# MotherBoard.net
KiCad netlist of a schematic drawn in Altium Designer
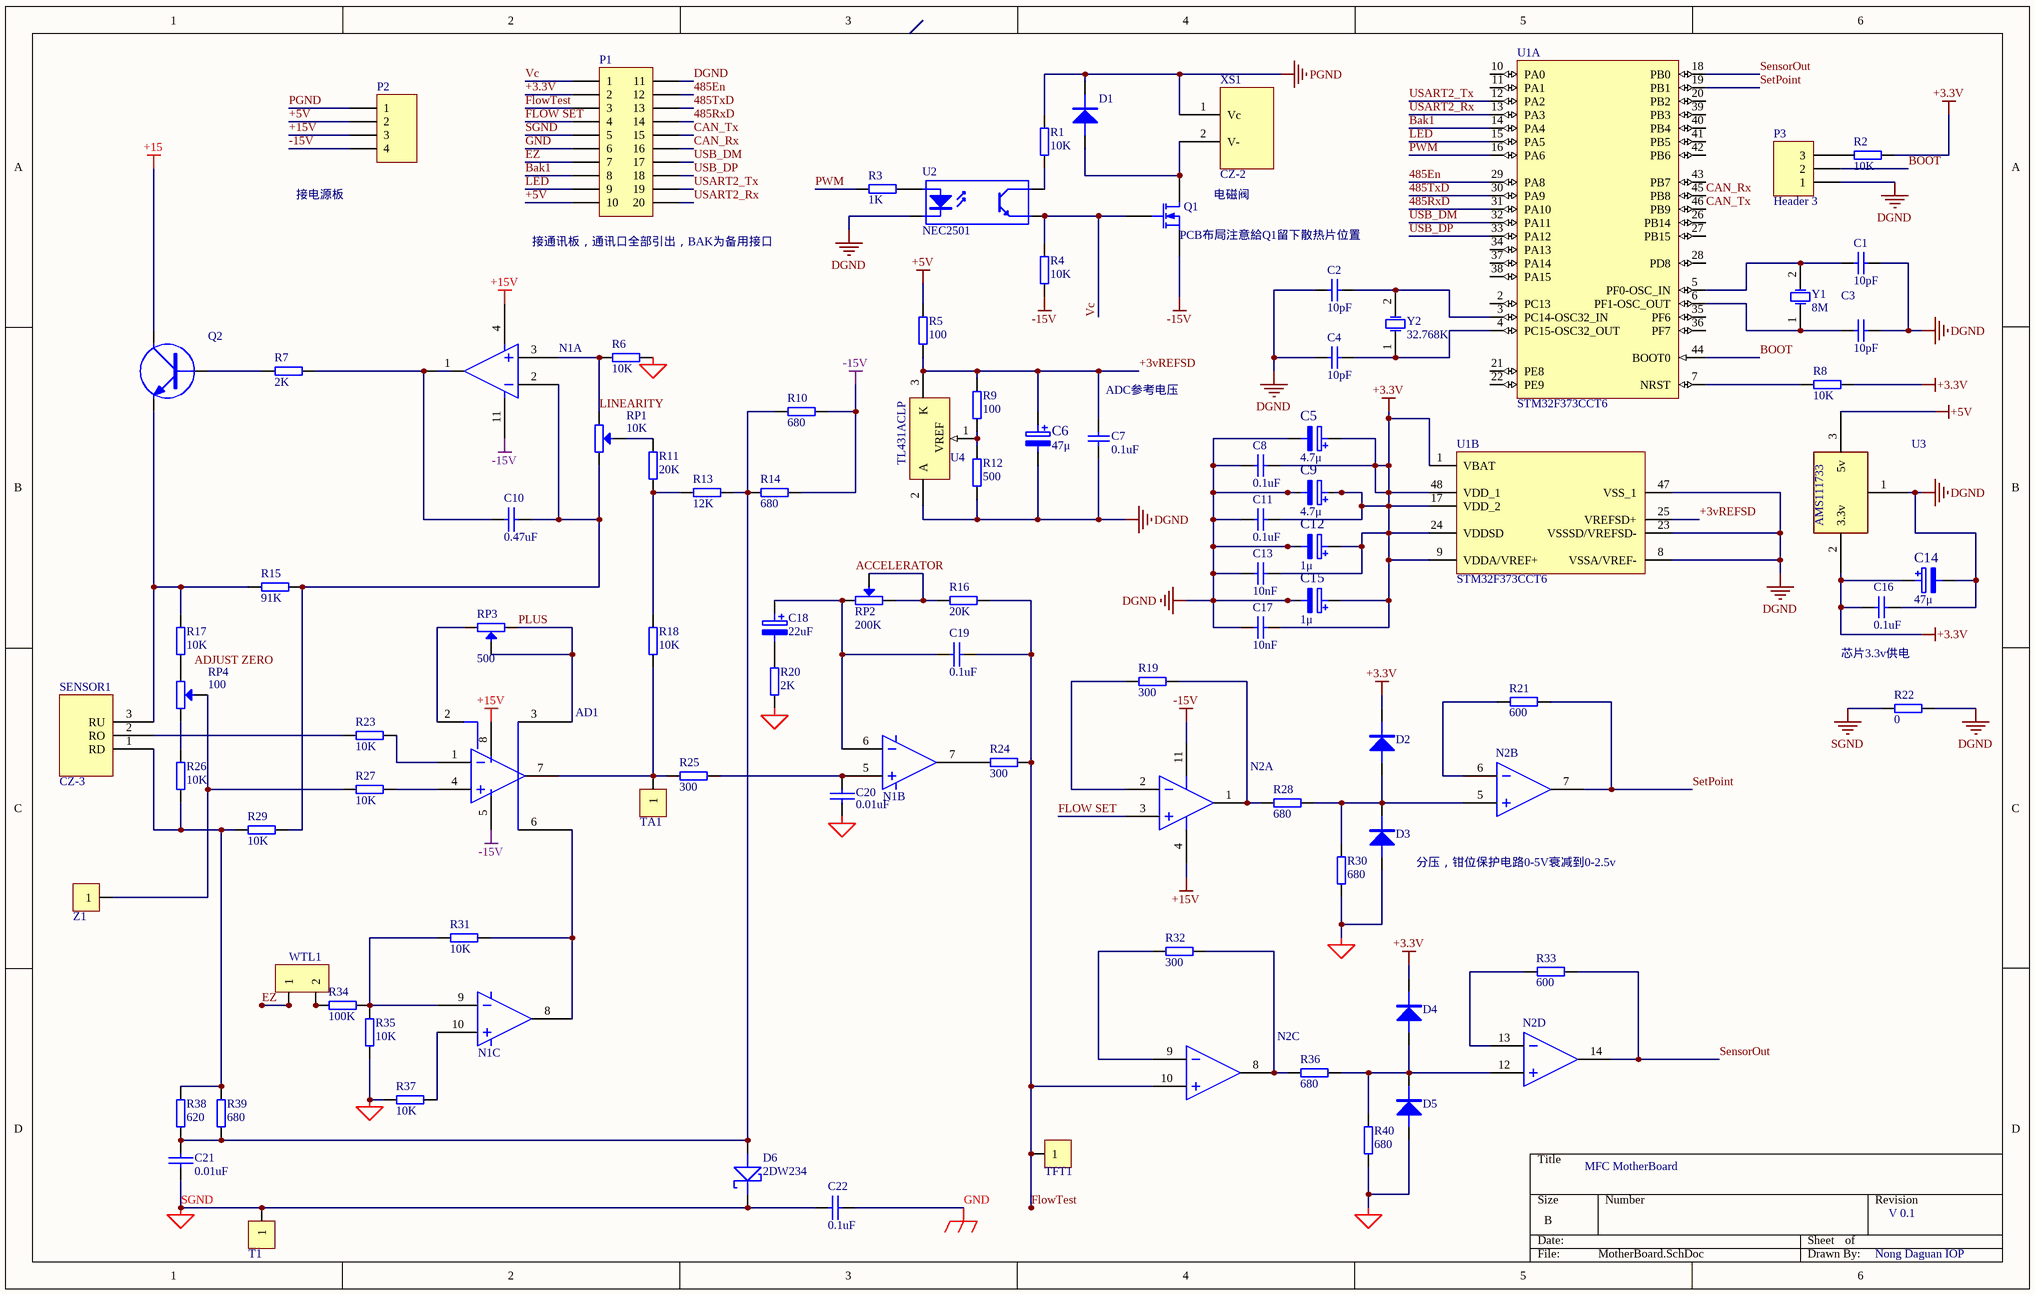
[diagram p0: MotherBoard.SchDoc]

(export (version "E")
  (design (tool "Eeschema 10.0.6"))
  (components
    (comp (ref "AD1") (value "~") (footprint "SO-8") (libsource (lib "1.60") (part "AD8221")))
    (comp (ref "C1")
      (value "10pF")
      (footprint "R.4")
      (description "Capacitor")
      (fields (field (name "PUBLISHER") "Altium Limited"))
      (libsource (lib "1.60") (part "Cap"))
    )
    (comp (ref "C2")
      (value "10pF")
      (footprint "R.4")
      (description "Capacitor")
      (fields (field (name "PUBLISHER") "Altium Limited"))
      (libsource (lib "1.60") (part "Cap"))
    )
    (comp (ref "C3")
      (value "10pF")
      (footprint "R.4")
      (description "Capacitor")
      (fields (field (name "PUBLISHER") "Altium Limited"))
      (libsource (lib "1.60") (part "Cap"))
    )
    (comp (ref "C4")
      (value "10pF")
      (footprint "R.4")
      (description "Capacitor")
      (fields (field (name "PUBLISHER") "Altium Limited"))
      (libsource (lib "1.60") (part "Cap"))
    )
    (comp (ref "C5") (value "4.7μ") (footprint "CA-22U") (libsource (lib "1.60") (part "ELECTRO2")))
    (comp (ref "C6") (value "47μ") (footprint "CA-22U") (libsource (lib "1.60") (part "ELECTRO2")))
    (comp (ref "C7")
      (value "0.1uF")
      (footprint "R.4")
      (description "Capacitor")
      (fields (field (name "PUBLISHER") "Altium Limited"))
      (libsource (lib "1.60") (part "Cap"))
    )
    (comp (ref "C8")
      (value "0.1uF")
      (footprint "R.4")
      (description "Capacitor")
      (fields (field (name "PUBLISHER") "Altium Limited"))
      (libsource (lib "1.60") (part "Cap"))
    )
    (comp (ref "C9") (value "4.7μ") (footprint "CA-22U") (libsource (lib "1.60") (part "ELECTRO2")))
    (comp (ref "C10") (value "0.47uF") (footprint "R.4") (libsource (lib "1.60") (part "CAP")))
    (comp (ref "C11")
      (value "0.1uF")
      (footprint "R.4")
      (description "Capacitor")
      (fields (field (name "PUBLISHER") "Altium Limited"))
      (libsource (lib "1.60") (part "Cap"))
    )
    (comp (ref "C12") (value "1μ") (footprint "CA-22U") (libsource (lib "1.60") (part "ELECTRO2")))
    (comp (ref "C13")
      (value "10nF")
      (footprint "R.4")
      (description "Capacitor")
      (fields (field (name "PUBLISHER") "Altium Limited"))
      (libsource (lib "1.60") (part "Cap"))
    )
    (comp (ref "C14") (value "47μ") (footprint "CA-22U") (libsource (lib "1.60") (part "ELECTRO2")))
    (comp (ref "C15") (value "1μ") (footprint "CA-22U") (libsource (lib "1.60") (part "ELECTRO2")))
    (comp (ref "C16")
      (value "0.1uF")
      (footprint "R.4")
      (description "Capacitor")
      (fields (field (name "PUBLISHER") "Altium Limited"))
      (libsource (lib "1.60") (part "Cap"))
    )
    (comp (ref "C17")
      (value "10nF")
      (footprint "R.4")
      (description "Capacitor")
      (fields (field (name "PUBLISHER") "Altium Limited"))
      (libsource (lib "1.60") (part "Cap"))
    )
    (comp (ref "C18") (value "22uF") (footprint "CA-22U") (libsource (lib "1.60") (part "ELECTRO2")))
    (comp (ref "C19") (value "0.1uF") (footprint "R.4") (libsource (lib "1.60") (part "CAP")))
    (comp (ref "C20") (value "0.01uF") (footprint "R.4") (libsource (lib "1.60") (part "CAP")))
    (comp (ref "C21") (value "0.01uF") (footprint "R.4") (libsource (lib "1.60") (part "CAP")))
    (comp (ref "C22") (value "0.1uF") (footprint "R.4") (libsource (lib "1.60") (part "CAP")))
    (comp (ref "D1") (value "2CK73C") (footprint "V.4") (libsource (lib "1.60") (part "DIODE")))
    (comp (ref "D2") (value "2CK73C") (footprint "DIODE") (libsource (lib "1.60") (part "DIODE")))
    (comp (ref "D3") (value "2CK73C") (footprint "DIODE") (libsource (lib "1.60") (part "DIODE")))
    (comp (ref "D4") (value "2CK73C") (footprint "DIODE") (libsource (lib "1.60") (part "DIODE")))
    (comp (ref "D5") (value "2CK73C") (footprint "DIODE") (libsource (lib "1.60") (part "DIODE")))
    (comp (ref "D6") (value "2DW234") (footprint "zena") (libsource (lib "1.90") (part "DIODE SCHOTTKY")))
    (comp (ref "N1") (value "LM124") (footprint "SO-14") (libsource (lib "*") (part "MFC7A.S01_LM124_56")))
    (comp (ref "N2") (value "LM124") (footprint "SO-14") (libsource (lib "1.60") (part "LM1241")))
    (comp (ref "P1")
      (value "~")
      (footprint "HDR2X10_CEN")
      (description "Header, 10-Pin, Dual row")
      (fields (field (name "PUBLISHER") "Altium Limited"))
      (libsource (lib "Miscellaneous Connectors") (part "Header 10X2A"))
    )
    (comp (ref "P2")
      (value "~")
      (footprint "HDR1X4")
      (description "Header, 4-Pin")
      (fields (field (name "PUBLISHER") "Altium Limited"))
      (libsource (lib "Miscellaneous Connectors") (part "Header 4"))
    )
    (comp (ref "P3")
      (value "Header 3")
      (footprint "HDR1X3")
      (description "Header, 3-Pin")
      (fields (field (name "PUBLISHER") "Altium Limited"))
      (libsource (lib "Miscellaneous Connectors") (part "Header 3"))
    )
    (comp (ref "Q1")
      (value "MOSFET-N")
      (footprint "TO-220AB")
      (description "N-Channel MOSFET")
      (fields (field (name "PUBLISHER") "Altium Limited"))
      (libsource (lib "Miscellaneous Devices") (part "MOSFET-N"))
    )
    (comp (ref "Q2") (value "MC9013") (footprint "BJT") (libsource (lib "1.60") (part "MC9013")))
    (comp (ref "R1") (value "10K") (footprint "R.4") (libsource (lib "1.60") (part "RES_1")))
    (comp (ref "R2") (value "10K") (footprint "R.4") (libsource (lib "1.60") (part "RES_1")))
    (comp (ref "R3") (value "1K") (footprint "R.4") (libsource (lib "1.60") (part "RES_1")))
    (comp (ref "R4") (value "10K") (footprint "R.4") (libsource (lib "1.60") (part "RES_1")))
    (comp (ref "R5") (value "100") (footprint "R.4") (libsource (lib "1.60") (part "RES_1")))
    (comp (ref "R6") (value "10K") (footprint "R.4") (libsource (lib "1.60") (part "RES_1")))
    (comp (ref "R7") (value "2K") (footprint "R.4") (libsource (lib "1.60") (part "RES_1")))
    (comp (ref "R8") (value "10K") (footprint "R.4") (libsource (lib "1.60") (part "RES_1")))
    (comp (ref "R9") (value "100") (footprint "RAD0.1") (libsource (lib "1.60") (part "RES")))
    (comp (ref "R10") (value "680") (footprint "R.4") (libsource (lib "1.60") (part "RES_1")))
    (comp (ref "R11") (value "20K") (footprint "R.4") (libsource (lib "1.60") (part "RES_1")))
    (comp (ref "R12") (value "500") (footprint "RAD0.1") (libsource (lib "1.60") (part "RES")))
    (comp (ref "R13") (value "12K") (footprint "R.4") (libsource (lib "1.60") (part "RES_1")))
    (comp (ref "R14") (value "680") (footprint "R.4") (libsource (lib "1.60") (part "RES_1")))
    (comp (ref "R15") (value "91K") (footprint "R.4") (libsource (lib "1.60") (part "RES_1")))
    (comp (ref "R16") (value "20K") (footprint "R.4") (libsource (lib "1.60") (part "RES_1")))
    (comp (ref "R17") (value "10K") (footprint "RAD0.1") (libsource (lib "1.60") (part "RES")))
    (comp (ref "R18") (value "10K") (footprint "R.4") (libsource (lib "1.60") (part "RES_1")))
    (comp (ref "R19") (value "300") (footprint "R.4") (libsource (lib "1.60") (part "RES_1")))
    (comp (ref "R20") (value "2K") (footprint "R.4") (libsource (lib "1.60") (part "RES_1")))
    (comp (ref "R21") (value "600") (footprint "R.4") (libsource (lib "1.60") (part "RES_1")))
    (comp (ref "R22") (value "0") (footprint "R.4") (libsource (lib "1.60") (part "RES_1")))
    (comp (ref "R23") (value "10K") (footprint "R.4") (libsource (lib "1.60") (part "RES_1")))
    (comp (ref "R24") (value "300") (footprint "R.4") (libsource (lib "1.60") (part "RES_1")))
    (comp (ref "R25") (value "300") (footprint "R.4") (libsource (lib "1.60") (part "RES_1")))
    (comp (ref "R26") (value "10K") (footprint "RAD0.1") (libsource (lib "1.60") (part "RES")))
    (comp (ref "R27") (value "10K") (footprint "R.4") (libsource (lib "1.60") (part "RES_1")))
    (comp (ref "R28") (value "680") (footprint "RAD0.1") (libsource (lib "1.60") (part "RES")))
    (comp (ref "R29") (value "10K") (footprint "R.4") (libsource (lib "1.60") (part "RES_1")))
    (comp (ref "R30") (value "680") (footprint "RAD0.1") (libsource (lib "1.60") (part "RES")))
    (comp (ref "R31") (value "10K") (footprint "R.4") (libsource (lib "1.60") (part "RES_1")))
    (comp (ref "R32") (value "300") (footprint "R.4") (libsource (lib "1.60") (part "RES_1")))
    (comp (ref "R33") (value "600") (footprint "R.4") (libsource (lib "1.60") (part "RES_1")))
    (comp (ref "R34") (value "100K") (footprint "R.4") (libsource (lib "1.60") (part "RES_1")))
    (comp (ref "R35") (value "10K") (footprint "R.4") (libsource (lib "1.60") (part "RES_1")))
    (comp (ref "R36") (value "680") (footprint "RAD0.1") (libsource (lib "1.60") (part "RES")))
    (comp (ref "R37") (value "10K") (footprint "R.4") (libsource (lib "1.60") (part "RES_1")))
    (comp (ref "R38") (value "620") (footprint "RAD0.1") (libsource (lib "1.60") (part "RES")))
    (comp (ref "R39") (value "680") (footprint "RAD0.1") (libsource (lib "1.60") (part "RES")))
    (comp (ref "R40") (value "680") (footprint "RAD0.1") (libsource (lib "1.60") (part "RES")))
    (comp (ref "RP1") (value "10K") (footprint "VR5132") (libsource (lib "1.60") (part "POT2")))
    (comp (ref "RP2")
      (value "200K")
      (footprint "changable res")
      (description "3362")
      (libsource (lib "1.60") (part "POT2"))
    )
    (comp (ref "RP3") (value "500") (footprint "VR5132") (libsource (lib "1.60") (part "POT2")))
    (comp (ref "RP4") (value "100") (footprint "VR5132") (libsource (lib "1.60") (part "POT2")))
    (comp (ref "SENSOR1") (value "CZ-3") (footprint "SENSOR") (libsource (lib "1.60") (part "CZ-3")))
    (comp (ref "T1") (value "CON1") (footprint "PAD - RECT") (libsource (lib "1.60") (part "CON1")))
    (comp (ref "TA1") (value "CON1") (footprint "PAD - RECT") (libsource (lib "1.60") (part "CON1")))
    (comp (ref "TFT1") (value "CON1") (footprint "PAD - RECT") (libsource (lib "") (part "CON1_1")))
    (comp (ref "U1")
      (value "STM32F373CCT6")
      (footprint "STM-LQFP48_N")
      (libsource (lib "1.60") (part "STM32F373CCT6"))
    )
    (comp (ref "U2")
      (value "NEC2501")
      (footprint "DIP-4")
      (description "4-Pin Phototransistor Optocoupler")
      (fields (field (name "PUBLISHER") "Altium Limited"))
      (libsource (lib "Miscellaneous Devices") (part "Optoisolator1"))
    )
    (comp (ref "U3") (value "AMS111733") (footprint "SOT223_N") (libsource (lib "1.60") (part "TL431")))
    (comp (ref "U4")
      (value "TL431ACLP")
      (footprint "LP03")
      (description "Adjustable Precision Shunt Regulator")
      (fields (field (name "PUBLISHER") "Altium Limited"))
      (libsource (lib "1.60") (part "TL431ACLP"))
    )
    (comp (ref "WTL1") (value "CON1") (footprint "ADJ") (libsource (lib "1.60") (part "CON1_1")))
    (comp (ref "XS1") (value "CZ-2") (footprint "VALVE") (libsource (lib "1.60") (part "CZ-2")))
    (comp (ref "Y1")
      (value "8M")
      (footprint "XTAL1")
      (description "Crystal Oscillator")
      (fields (field (name "PUBLISHER") "Altium Limited"))
      (libsource (lib "1.60") (part "XTAL"))
    )
    (comp (ref "Y2")
      (value "32.768K")
      (footprint "XTAL1")
      (description "Crystal Oscillator")
      (fields (field (name "PUBLISHER") "Altium Limited"))
      (libsource (lib "1.60") (part "XTAL"))
    )
    (comp (ref "Z1") (value "CON1") (footprint "PAD - RECT") (libsource (lib "") (part "CON1_2")))
  )
  (nets
    (net (code "1") (name "+3.3V") (class "Default")
      (node (ref "C11") (pin "2") (pinfunction "2_2") (pintype "passive"))
      (node (ref "C12") (pin "1") (pintype "passive"))
      (node (ref "C13") (pin "2") (pinfunction "2_2") (pintype "passive"))
      (node (ref "C14") (pin "1") (pintype "passive"))
      (node (ref "C15") (pin "1") (pintype "passive"))
      (node (ref "C16") (pin "1") (pinfunction "1_1") (pintype "passive"))
      (node (ref "C17") (pin "2") (pinfunction "2_2") (pintype "passive"))
      (node (ref "C5") (pin "1") (pintype "passive"))
      (node (ref "C8") (pin "2") (pinfunction "2_2") (pintype "passive"))
      (node (ref "C9") (pin "1") (pintype "passive"))
      (node (ref "D2") (pin "K") (pintype "passive"))
      (node (ref "D4") (pin "K") (pintype "passive"))
      (node (ref "P1") (pin "2") (pinfunction "2_2") (pintype "passive"))
      (node (ref "R2") (pin "2") (pintype "passive"))
      (node (ref "R8") (pin "2") (pintype "passive"))
      (node (ref "U1") (pin "1") (pinfunction "VBAT_1") (pintype "power_in"))
      (node (ref "U1") (pin "17") (pinfunction "VDD_2_17") (pintype "power_in"))
      (node (ref "U1") (pin "24") (pinfunction "VDDSD_24") (pintype "power_in"))
      (node (ref "U1") (pin "48") (pinfunction "VDD_1_48") (pintype "power_in"))
      (node (ref "U1") (pin "9") (pinfunction "VDDA/VREF+_9") (pintype "power_in"))
      (node (ref "U3") (pin "2") (pinfunction "3.3v_2") (pintype "passive"))
    )
    (net (code "2") (name "+5V") (class "Default")
      (node (ref "P1") (pin "10") (pinfunction "10_10") (pintype "passive"))
      (node (ref "P2") (pin "2") (pinfunction "2_2") (pintype "passive"))
      (node (ref "R5") (pin "2") (pintype "passive"))
      (node (ref "U3") (pin "3") (pinfunction "5v_3") (pintype "passive"))
    )
    (net (code "3") (name "+15") (class "Default")
      (node (ref "Q2") (pin "C") (pinfunction "C_C") (pintype "passive"))
    )
    (net (code "4") (name "+15V") (class "Default")
      (node (ref "AD1") (pin "8") (pinfunction "8_8") (pintype "passive"))
      (node (ref "N1") (pin "4") (pintype "passive"))
      (node (ref "N2") (pin "4") (pinfunction "V+_4") (pintype "passive"))
      (node (ref "P2") (pin "3") (pinfunction "3_3") (pintype "passive"))
    )
    (net (code "5") (name "-15V") (class "Default")
      (node (ref "AD1") (pin "5") (pinfunction "5_5") (pintype "passive"))
      (node (ref "N1") (pin "11") (pintype "passive"))
      (node (ref "N2") (pin "11") (pinfunction "GND_11") (pintype "passive"))
      (node (ref "P2") (pin "4") (pinfunction "4_4") (pintype "passive"))
      (node (ref "Q1") (pin "3") (pinfunction "S_3") (pintype "passive"))
      (node (ref "R10") (pin "2") (pintype "passive"))
      (node (ref "R14") (pin "2") (pintype "passive"))
      (node (ref "R4") (pin "1") (pintype "passive"))
    )
    (net (code "6") (name "/+3vREFSD") (class "Default")
      (node (ref "C6") (pin "1") (pintype "passive"))
      (node (ref "C7") (pin "2") (pinfunction "2_2") (pintype "passive"))
      (node (ref "R5") (pin "1") (pintype "passive"))
      (node (ref "R9") (pin "1") (pintype "passive"))
      (node (ref "U1") (pin "25") (pinfunction "VREFSD+_25") (pintype "power_in"))
      (node (ref "U4") (pin "3") (pinfunction "K_3") (pintype "power_in"))
    )
    (net (code "7") (name "/485En") (class "Default")
      (node (ref "P1") (pin "12") (pinfunction "12_12") (pintype "passive"))
      (node (ref "U1") (pin "29") (pinfunction "PA8_29") (pintype "bidirectional"))
    )
    (net (code "8") (name "/485RxD") (class "Default")
      (node (ref "P1") (pin "14") (pinfunction "14_14") (pintype "passive"))
      (node (ref "U1") (pin "31") (pinfunction "PA10_31") (pintype "bidirectional"))
    )
    (net (code "9") (name "/485TxD") (class "Default")
      (node (ref "P1") (pin "13") (pinfunction "13_13") (pintype "passive"))
      (node (ref "U1") (pin "30") (pinfunction "PA9_30") (pintype "bidirectional"))
    )
    (net (code "11") (name "/BOOT") (class "Default")
      (node (ref "P3") (pin "2") (pinfunction "2_2") (pintype "passive"))
      (node (ref "U1") (pin "44") (pinfunction "BOOT0_44") (pintype "input"))
    )
    (net (code "12") (name "/Bak1") (class "Default")
      (node (ref "P1") (pin "8") (pinfunction "8_8") (pintype "passive"))
      (node (ref "U1") (pin "14") (pinfunction "PA4_14") (pintype "bidirectional"))
    )
    (net (code "13") (name "/CAN_Rx") (class "Default")
      (node (ref "P1") (pin "16") (pinfunction "16_16") (pintype "passive"))
      (node (ref "U1") (pin "45") (pinfunction "PB8_45") (pintype "bidirectional"))
    )
    (net (code "14") (name "/CAN_Tx") (class "Default")
      (node (ref "P1") (pin "15") (pinfunction "15_15") (pintype "passive"))
      (node (ref "U1") (pin "46") (pinfunction "PB9_46") (pintype "bidirectional"))
    )
    (net (code "15") (name "/EZ") (class "Default")
      (node (ref "P1") (pin "7") (pinfunction "7_7") (pintype "passive"))
      (node (ref "WTL1") (pin "1") (pinfunction "1_1") (pintype "passive"))
    )
    (net (code "16") (name "/FLOW SET") (class "Default")
      (node (ref "N2") (pin "3") (pinfunction "INPUT1+_3") (pintype "passive"))
      (node (ref "P1") (pin "4") (pinfunction "4_4") (pintype "passive"))
    )
    (net (code "17") (name "/FlowTest") (class "Default")
      (node (ref "C19") (pin "2") (pintype "passive"))
      (node (ref "N2") (pin "10") (pinfunction "INPUT3+_10") (pintype "passive"))
      (node (ref "P1") (pin "3") (pinfunction "3_3") (pintype "passive"))
      (node (ref "R16") (pin "2") (pintype "passive"))
      (node (ref "R24") (pin "2") (pintype "passive"))
      (node (ref "TFT1") (pin "1") (pinfunction "1_1") (pintype "passive"))
    )
    (net (code "18") (name "/LED") (class "Default")
      (node (ref "P1") (pin "9") (pinfunction "9_9") (pintype "passive"))
      (node (ref "U1") (pin "15") (pinfunction "PA5_15") (pintype "bidirectional"))
    )
    (net (code "19") (name "/PWM") (class "Default")
      (node (ref "R3") (pin "1") (pintype "passive"))
      (node (ref "U1") (pin "16") (pinfunction "PA6_16") (pintype "bidirectional"))
    )
    (net (code "20") (name "/SensorOut") (class "Default")
      (node (ref "N2") (pin "14") (pinfunction "OUTPUT4_14") (pintype "passive"))
      (node (ref "R33") (pin "2") (pintype "passive"))
      (node (ref "U1") (pin "18") (pinfunction "PB0_18") (pintype "bidirectional"))
    )
    (net (code "21") (name "/SetPoint") (class "Default")
      (node (ref "N2") (pin "7") (pinfunction "OUTPUT2_7") (pintype "passive"))
      (node (ref "R21") (pin "2") (pintype "passive"))
      (node (ref "U1") (pin "19") (pinfunction "PB1_19") (pintype "bidirectional"))
    )
    (net (code "22") (name "/USART2_Rx") (class "Default")
      (node (ref "P1") (pin "20") (pinfunction "20_20") (pintype "passive"))
      (node (ref "U1") (pin "13") (pinfunction "PA3_13") (pintype "bidirectional"))
    )
    (net (code "23") (name "/USART2_Tx") (class "Default")
      (node (ref "P1") (pin "19") (pinfunction "19_19") (pintype "passive"))
      (node (ref "U1") (pin "12") (pinfunction "PA2_12") (pintype "bidirectional"))
    )
    (net (code "24") (name "/USB_DM") (class "Default")
      (node (ref "P1") (pin "17") (pinfunction "17_17") (pintype "passive"))
      (node (ref "U1") (pin "32") (pinfunction "PA11_32") (pintype "bidirectional"))
    )
    (net (code "25") (name "/USB_DP") (class "Default")
      (node (ref "P1") (pin "18") (pinfunction "18_18") (pintype "passive"))
      (node (ref "U1") (pin "33") (pinfunction "PA12_33") (pintype "bidirectional"))
    )
    (net (code "26") (name "/Vc") (class "Default")
      (node (ref "P1") (pin "1") (pinfunction "1_1") (pintype "passive"))
      (node (ref "Q1") (pin "1") (pinfunction "G_1") (pintype "passive"))
      (node (ref "R4") (pin "2") (pintype "passive"))
      (node (ref "U2") (pin "3") (pinfunction "E_3") (pintype "passive"))
    )
    (net (code "27") (name "DGND") (class "Default")
      (node (ref "C1") (pin "2") (pinfunction "2_2") (pintype "passive"))
      (node (ref "C11") (pin "1") (pinfunction "1_1") (pintype "passive"))
      (node (ref "C12") (pin "2") (pintype "passive"))
      (node (ref "C13") (pin "1") (pinfunction "1_1") (pintype "passive"))
      (node (ref "C14") (pin "2") (pintype "passive"))
      (node (ref "C15") (pin "2") (pintype "passive"))
      (node (ref "C16") (pin "2") (pinfunction "2_2") (pintype "passive"))
      (node (ref "C17") (pin "1") (pinfunction "1_1") (pintype "passive"))
      (node (ref "C2") (pin "1") (pinfunction "1_1") (pintype "passive"))
      (node (ref "C3") (pin "2") (pinfunction "2_2") (pintype "passive"))
      (node (ref "C4") (pin "1") (pinfunction "1_1") (pintype "passive"))
      (node (ref "C5") (pin "2") (pintype "passive"))
      (node (ref "C6") (pin "2") (pintype "passive"))
      (node (ref "C7") (pin "1") (pinfunction "1_1") (pintype "passive"))
      (node (ref "C8") (pin "1") (pinfunction "1_1") (pintype "passive"))
      (node (ref "C9") (pin "2") (pintype "passive"))
      (node (ref "P1") (pin "11") (pinfunction "11_11") (pintype "passive"))
      (node (ref "P3") (pin "1") (pinfunction "1_1") (pintype "passive"))
      (node (ref "R12") (pin "1") (pintype "passive"))
      (node (ref "R22") (pin "2") (pintype "passive"))
      (node (ref "U1") (pin "23") (pinfunction "VSSSD/VREFSD-_23") (pintype "power_in"))
      (node (ref "U1") (pin "47") (pinfunction "VSS_1_47") (pintype "power_in"))
      (node (ref "U1") (pin "8") (pinfunction "VSSA/VREF-_8") (pintype "power_in"))
      (node (ref "U2") (pin "2") (pinfunction "K_2") (pintype "passive"))
      (node (ref "U3") (pin "1") (pinfunction "GND_1") (pintype "passive"))
      (node (ref "U4") (pin "2") (pinfunction "A_2") (pintype "power_in"))
    )
    (net (code "28") (name "GND") (class "Default")
      (node (ref "C22") (pin "2") (pintype "passive"))
      (node (ref "P1") (pin "6") (pinfunction "6_6") (pintype "passive"))
    )
    (net (code "29") (name "Net-(AD1-Pad1)") (class "Default")
      (node (ref "AD1") (pin "1") (pinfunction "1_1") (pintype "passive"))
      (node (ref "R23") (pin "2") (pintype "passive"))
    )
    (net (code "30") (name "Net-(AD1-Pad2)") (class "Default")
      (node (ref "AD1") (pin "2") (pinfunction "2_2") (pintype "passive"))
      (node (ref "RP3") (pin "2") (pinfunction "2_2") (pintype "passive"))
    )
    (net (code "31") (name "Net-(AD1-Pad3)") (class "Default")
      (node (ref "AD1") (pin "3") (pinfunction "3_3") (pintype "passive"))
      (node (ref "RP3") (pin "1") (pinfunction "1_1") (pintype "passive"))
      (node (ref "RP3") (pin "3") (pinfunction "3_3") (pintype "passive"))
    )
    (net (code "32") (name "Net-(AD1-Pad4)") (class "Default")
      (node (ref "AD1") (pin "4") (pinfunction "4_4") (pintype "passive"))
      (node (ref "R27") (pin "2") (pintype "passive"))
    )
    (net (code "33") (name "Net-(AD1-Pad6)") (class "Default")
      (node (ref "AD1") (pin "6") (pinfunction "6_6") (pintype "passive"))
      (node (ref "N1") (pin "8") (pintype "passive"))
      (node (ref "R31") (pin "2") (pintype "passive"))
    )
    (net (code "34") (name "Net-(AD1-Pad7)") (class "Default")
      (node (ref "AD1") (pin "7") (pinfunction "7_7") (pintype "passive"))
      (node (ref "R18") (pin "1") (pintype "passive"))
      (node (ref "R25") (pin "1") (pintype "passive"))
      (node (ref "TA1") (pin "1") (pinfunction "1_1") (pintype "passive"))
    )
    (net (code "35") (name "Net-(C10-Pad1)") (class "Default")
      (node (ref "C10") (pin "1") (pintype "passive"))
      (node (ref "N1") (pin "1") (pintype "passive"))
      (node (ref "R7") (pin "2") (pintype "passive"))
    )
    (net (code "36") (name "Net-(C10-Pad2)") (class "Default")
      (node (ref "C10") (pin "2") (pintype "passive"))
      (node (ref "N1") (pin "2") (pintype "passive"))
      (node (ref "R15") (pin "2") (pintype "passive"))
      (node (ref "R29") (pin "2") (pintype "passive"))
      (node (ref "RP1") (pin "2") (pinfunction "2_2") (pintype "passive"))
    )
    (net (code "37") (name "Net-(C18-Pad1)") (class "Default")
      (node (ref "C18") (pin "1") (pintype "passive"))
      (node (ref "C19") (pin "1") (pintype "passive"))
      (node (ref "N1") (pin "6") (pintype "passive"))
      (node (ref "RP2") (pin "1") (pinfunction "1_1") (pintype "passive"))
    )
    (net (code "38") (name "Net-(C18-Pad2)") (class "Default")
      (node (ref "C18") (pin "2") (pintype "passive"))
      (node (ref "R20") (pin "2") (pintype "passive"))
    )
    (net (code "39") (name "Net-(C20-Pad2)") (class "Default")
      (node (ref "C20") (pin "2") (pintype "passive"))
      (node (ref "N1") (pin "5") (pintype "passive"))
      (node (ref "R25") (pin "2") (pintype "passive"))
    )
    (net (code "40") (name "Net-(D6-ANODE)") (class "Default")
      (node (ref "C21") (pin "1") (pintype "passive"))
      (node (ref "D6") (pin "A") (pinfunction "ANODE_A") (pintype "passive"))
      (node (ref "R10") (pin "1") (pintype "passive"))
      (node (ref "R13") (pin "2") (pintype "passive"))
      (node (ref "R14") (pin "1") (pintype "passive"))
      (node (ref "R38") (pin "1") (pintype "passive"))
      (node (ref "R39") (pin "1") (pintype "passive"))
    )
    (net (code "41") (name "Net-(N1-Pad3)") (class "Default")
      (node (ref "N1") (pin "3") (pintype "passive"))
      (node (ref "R6") (pin "1") (pintype "passive"))
      (node (ref "RP1") (pin "1") (pinfunction "1_1") (pintype "passive"))
    )
    (net (code "42") (name "Net-(N1-Pad7)") (class "Default")
      (node (ref "N1") (pin "7") (pintype "passive"))
      (node (ref "R24") (pin "1") (pintype "passive"))
    )
    (net (code "43") (name "Net-(N1-Pad9)") (class "Default")
      (node (ref "N1") (pin "9") (pintype "passive"))
      (node (ref "R31") (pin "1") (pintype "passive"))
      (node (ref "R34") (pin "2") (pintype "passive"))
      (node (ref "R35") (pin "2") (pintype "passive"))
    )
    (net (code "44") (name "Net-(N1-Pad10)") (class "Default")
      (node (ref "N1") (pin "10") (pintype "passive"))
      (node (ref "R37") (pin "1") (pintype "passive"))
    )
    (net (code "45") (name "Net-(N2A-INPUT1-)") (class "Default")
      (node (ref "N2") (pin "2") (pinfunction "INPUT1-_2") (pintype "passive"))
      (node (ref "R19") (pin "1") (pintype "passive"))
    )
    (net (code "46") (name "Net-(N2A-OUTPUT1)") (class "Default")
      (node (ref "N2") (pin "1") (pinfunction "OUTPUT1_1") (pintype "passive"))
      (node (ref "R19") (pin "2") (pintype "passive"))
      (node (ref "R28") (pin "2") (pintype "passive"))
    )
    (net (code "47") (name "Net-(N2B-INPUT2-)") (class "Default")
      (node (ref "N2") (pin "6") (pinfunction "INPUT2-_6") (pintype "passive"))
      (node (ref "R21") (pin "1") (pintype "passive"))
    )
    (net (code "48") (name "Net-(N2B-INTPUT2+)") (class "Default")
      (node (ref "D2") (pin "A") (pintype "passive"))
      (node (ref "D3") (pin "K") (pintype "passive"))
      (node (ref "N2") (pin "5") (pinfunction "INTPUT2+_5") (pintype "passive"))
      (node (ref "R28") (pin "1") (pintype "passive"))
      (node (ref "R30") (pin "2") (pintype "passive"))
    )
    (net (code "49") (name "Net-(N2C-INPUT3-)") (class "Default")
      (node (ref "N2") (pin "9") (pinfunction "INPUT3-_9") (pintype "passive"))
      (node (ref "R32") (pin "1") (pintype "passive"))
    )
    (net (code "50") (name "Net-(N2C-OUTPUT3)") (class "Default")
      (node (ref "N2") (pin "8") (pinfunction "OUTPUT3_8") (pintype "passive"))
      (node (ref "R32") (pin "2") (pintype "passive"))
      (node (ref "R36") (pin "2") (pintype "passive"))
    )
    (net (code "51") (name "Net-(N2D-INPUT4+)") (class "Default")
      (node (ref "D4") (pin "A") (pintype "passive"))
      (node (ref "D5") (pin "K") (pintype "passive"))
      (node (ref "N2") (pin "12") (pinfunction "INPUT4+_12") (pintype "passive"))
      (node (ref "R36") (pin "1") (pintype "passive"))
      (node (ref "R40") (pin "2") (pintype "passive"))
    )
    (net (code "52") (name "Net-(N2D-INPUT4-)") (class "Default")
      (node (ref "N2") (pin "13") (pinfunction "INPUT4-_13") (pintype "passive"))
      (node (ref "R33") (pin "1") (pintype "passive"))
    )
    (net (code "53") (name "Net-(P3-Pad3)") (class "Default")
      (node (ref "P3") (pin "3") (pinfunction "3_3") (pintype "passive"))
      (node (ref "R2") (pin "1") (pintype "passive"))
    )
    (net (code "54") (name "Net-(Q1-D)") (class "Default")
      (node (ref "D1") (pin "A") (pintype "passive"))
      (node (ref "Q1") (pin "2") (pinfunction "D_2") (pintype "passive"))
      (node (ref "XS1") (pin "2") (pinfunction "V-_2") (pintype "passive"))
    )
    (net (code "55") (name "Net-(Q2-PadB)") (class "Default")
      (node (ref "Q2") (pin "B") (pinfunction "B_B") (pintype "passive"))
      (node (ref "R7") (pin "1") (pintype "passive"))
    )
    (net (code "56") (name "Net-(R11-Pad1)") (class "Default")
      (node (ref "R11") (pin "1") (pintype "passive"))
      (node (ref "R13") (pin "1") (pintype "passive"))
      (node (ref "R18") (pin "2") (pintype "passive"))
    )
    (net (code "57") (name "Net-(R11-Pad2)") (class "Default")
      (node (ref "R11") (pin "2") (pintype "passive"))
      (node (ref "RP1") (pin "3") (pinfunction "3_3") (pintype "passive"))
    )
    (net (code "58") (name "Net-(R16-Pad1)") (class "Default")
      (node (ref "R16") (pin "1") (pintype "passive"))
      (node (ref "RP2") (pin "2") (pinfunction "2_2") (pintype "passive"))
      (node (ref "RP2") (pin "3") (pinfunction "3_3") (pintype "passive"))
    )
    (net (code "59") (name "Net-(R17-Pad1)") (class "Default")
      (node (ref "R17") (pin "1") (pintype "passive"))
      (node (ref "RP4") (pin "1") (pinfunction "1_1") (pintype "passive"))
    )
    (net (code "60") (name "Net-(R26-Pad2)") (class "Default")
      (node (ref "R26") (pin "2") (pintype "passive"))
      (node (ref "RP4") (pin "2") (pinfunction "2_2") (pintype "passive"))
    )
    (net (code "61") (name "Net-(R27-Pad1)") (class "Default")
      (node (ref "R27") (pin "1") (pintype "passive"))
      (node (ref "RP4") (pin "3") (pinfunction "3_3") (pintype "passive"))
      (node (ref "Z1") (pin "1") (pinfunction "1_1") (pintype "passive"))
    )
    (net (code "62") (name "Net-(R34-Pad1)") (class "Default")
      (node (ref "R34") (pin "1") (pintype "passive"))
      (node (ref "WTL1") (pin "2") (pinfunction "2_2") (pintype "passive"))
    )
    (net (code "63") (name "Net-(SENSOR1-RD)") (class "Default")
      (node (ref "R26") (pin "1") (pintype "passive"))
      (node (ref "R29") (pin "1") (pintype "passive"))
      (node (ref "R38") (pin "2") (pintype "passive"))
      (node (ref "R39") (pin "2") (pintype "passive"))
      (node (ref "SENSOR1") (pin "1") (pinfunction "RD_1") (pintype "passive"))
    )
    (net (code "64") (name "Net-(SENSOR1-RO)") (class "Default")
      (node (ref "R23") (pin "1") (pintype "passive"))
      (node (ref "SENSOR1") (pin "2") (pinfunction "RO_2") (pintype "passive"))
    )
    (net (code "65") (name "Net-(SENSOR1-RU)") (class "Default")
      (node (ref "Q2") (pin "E") (pinfunction "E_E") (pintype "passive"))
      (node (ref "R15") (pin "1") (pintype "passive"))
      (node (ref "R17") (pin "2") (pintype "passive"))
      (node (ref "SENSOR1") (pin "3") (pinfunction "RU_3") (pintype "passive"))
    )
    (net (code "66") (name "Net-(U1A-NRST)") (class "Default")
      (node (ref "R8") (pin "1") (pintype "passive"))
      (node (ref "U1") (pin "7") (pinfunction "NRST_7") (pintype "bidirectional"))
    )
    (net (code "67") (name "Net-(U1A-PC14-OSC32_IN)") (class "Default")
      (node (ref "C2") (pin "2") (pinfunction "2_2") (pintype "passive"))
      (node (ref "U1") (pin "3") (pinfunction "PC14-OSC32_IN_3") (pintype "bidirectional"))
      (node (ref "Y2") (pin "2") (pinfunction "OSC2_2") (pintype "passive"))
    )
    (net (code "68") (name "Net-(U1A-PC15-OSC32_OUT)") (class "Default")
      (node (ref "C4") (pin "2") (pinfunction "2_2") (pintype "passive"))
      (node (ref "U1") (pin "4") (pinfunction "PC15-OSC32_OUT_4") (pintype "bidirectional"))
      (node (ref "Y2") (pin "1") (pinfunction "OSC1_1") (pintype "passive"))
    )
    (net (code "69") (name "Net-(U1A-PF0-OSC_IN)") (class "Default")
      (node (ref "C1") (pin "1") (pinfunction "1_1") (pintype "passive"))
      (node (ref "U1") (pin "5") (pinfunction "PF0-OSC_IN_5") (pintype "bidirectional"))
      (node (ref "Y1") (pin "2") (pinfunction "OSC2_2") (pintype "passive"))
    )
    (net (code "70") (name "Net-(U1A-PF1-OSC_OUT)") (class "Default")
      (node (ref "C3") (pin "1") (pinfunction "1_1") (pintype "passive"))
      (node (ref "U1") (pin "6") (pinfunction "PF1-OSC_OUT_6") (pintype "bidirectional"))
      (node (ref "Y1") (pin "1") (pinfunction "OSC1_1") (pintype "passive"))
    )
    (net (code "71") (name "Net-(U2-A)") (class "Default")
      (node (ref "R3") (pin "2") (pintype "passive"))
      (node (ref "U2") (pin "1") (pinfunction "A_1") (pintype "passive"))
    )
    (net (code "72") (name "Net-(U2-C)") (class "Default")
      (node (ref "R1") (pin "1") (pintype "passive"))
      (node (ref "U2") (pin "4") (pinfunction "C_4") (pintype "passive"))
    )
    (net (code "73") (name "Net-(U4-VREF)") (class "Default")
      (node (ref "R12") (pin "2") (pintype "passive"))
      (node (ref "R9") (pin "2") (pintype "passive"))
      (node (ref "U4") (pin "1") (pinfunction "VREF_1") (pintype "input"))
    )
    (net (code "74") (name "PGND") (class "Default")
      (node (ref "D1") (pin "K") (pintype "passive"))
      (node (ref "P2") (pin "1") (pinfunction "1_1") (pintype "passive"))
      (node (ref "R1") (pin "2") (pintype "passive"))
      (node (ref "XS1") (pin "1") (pinfunction "Vc_1") (pintype "passive"))
    )
    (net (code "75") (name "SGND") (class "Default")
      (node (ref "C20") (pin "1") (pintype "passive"))
      (node (ref "C21") (pin "2") (pintype "passive"))
      (node (ref "C22") (pin "1") (pintype "passive"))
      (node (ref "D3") (pin "A") (pintype "passive"))
      (node (ref "D5") (pin "A") (pintype "passive"))
      (node (ref "D6") (pin "K") (pinfunction "CATHODE_K") (pintype "passive"))
      (node (ref "P1") (pin "5") (pinfunction "5_5") (pintype "passive"))
      (node (ref "R20") (pin "1") (pintype "passive"))
      (node (ref "R22") (pin "1") (pintype "passive"))
      (node (ref "R30") (pin "1") (pintype "passive"))
      (node (ref "R35") (pin "1") (pintype "passive"))
      (node (ref "R37") (pin "2") (pintype "passive"))
      (node (ref "R40") (pin "1") (pintype "passive"))
      (node (ref "R6") (pin "2") (pintype "passive"))
      (node (ref "T1") (pin "1") (pinfunction "1_1") (pintype "passive"))
    )
    (net (code "76") (name "unconnected-(U1A-PA0-Pad10)") (class "Default")
      (node (ref "U1") (pin "10") (pinfunction "PA0_10") (pintype "bidirectional"))
    )
    (net (code "77") (name "unconnected-(U1A-PA1-Pad11)") (class "Default")
      (node (ref "U1") (pin "11") (pinfunction "PA1_11") (pintype "bidirectional"))
    )
    (net (code "78") (name "unconnected-(U1A-PA13-Pad34)") (class "Default")
      (node (ref "U1") (pin "34") (pinfunction "PA13_34") (pintype "bidirectional"))
    )
    (net (code "79") (name "unconnected-(U1A-PA14-Pad37)") (class "Default")
      (node (ref "U1") (pin "37") (pinfunction "PA14_37") (pintype "bidirectional"))
    )
    (net (code "80") (name "unconnected-(U1A-PA15-Pad38)") (class "Default")
      (node (ref "U1") (pin "38") (pinfunction "PA15_38") (pintype "bidirectional"))
    )
    (net (code "81") (name "unconnected-(U1A-PB2-Pad20)") (class "Default")
      (node (ref "U1") (pin "20") (pinfunction "PB2_20") (pintype "bidirectional"))
    )
    (net (code "82") (name "unconnected-(U1A-PB3-Pad39)") (class "Default")
      (node (ref "U1") (pin "39") (pinfunction "PB3_39") (pintype "bidirectional"))
    )
    (net (code "83") (name "unconnected-(U1A-PB4-Pad40)") (class "Default")
      (node (ref "U1") (pin "40") (pinfunction "PB4_40") (pintype "bidirectional"))
    )
    (net (code "84") (name "unconnected-(U1A-PB5-Pad41)") (class "Default")
      (node (ref "U1") (pin "41") (pinfunction "PB5_41") (pintype "bidirectional"))
    )
    (net (code "85") (name "unconnected-(U1A-PB6-Pad42)") (class "Default")
      (node (ref "U1") (pin "42") (pinfunction "PB6_42") (pintype "bidirectional"))
    )
    (net (code "86") (name "unconnected-(U1A-PB7-Pad43)") (class "Default")
      (node (ref "U1") (pin "43") (pinfunction "PB7_43") (pintype "bidirectional"))
    )
    (net (code "87") (name "unconnected-(U1A-PB14-Pad26)") (class "Default")
      (node (ref "U1") (pin "26") (pinfunction "PB14_26") (pintype "bidirectional"))
    )
    (net (code "88") (name "unconnected-(U1A-PB15-Pad27)") (class "Default")
      (node (ref "U1") (pin "27") (pinfunction "PB15_27") (pintype "bidirectional"))
    )
    (net (code "89") (name "unconnected-(U1A-PC13-Pad2)") (class "Default")
      (node (ref "U1") (pin "2") (pinfunction "PC13_2") (pintype "bidirectional"))
    )
    (net (code "90") (name "unconnected-(U1A-PD8-Pad28)") (class "Default")
      (node (ref "U1") (pin "28") (pinfunction "PD8_28") (pintype "bidirectional"))
    )
    (net (code "91") (name "unconnected-(U1A-PE8-Pad21)") (class "Default")
      (node (ref "U1") (pin "21") (pinfunction "PE8_21") (pintype "bidirectional"))
    )
    (net (code "92") (name "unconnected-(U1A-PE9-Pad22)") (class "Default")
      (node (ref "U1") (pin "22") (pinfunction "PE9_22") (pintype "bidirectional"))
    )
    (net (code "93") (name "unconnected-(U1A-PF6-Pad35)") (class "Default")
      (node (ref "U1") (pin "35") (pinfunction "PF6_35") (pintype "bidirectional"))
    )
    (net (code "94") (name "unconnected-(U1A-PF7-Pad36)") (class "Default")
      (node (ref "U1") (pin "36") (pinfunction "PF7_36") (pintype "bidirectional"))
    )
    (net (code "95") (name "unconnected-(U3-Pad4)") (class "Default")
      (node (ref "U3") (pin "4") (pinfunction "4_4") (pintype "passive"))
    )
  )
)
